# plp-ctop_2a.net
KiCad netlist of a schematic drawn in Altium Designer
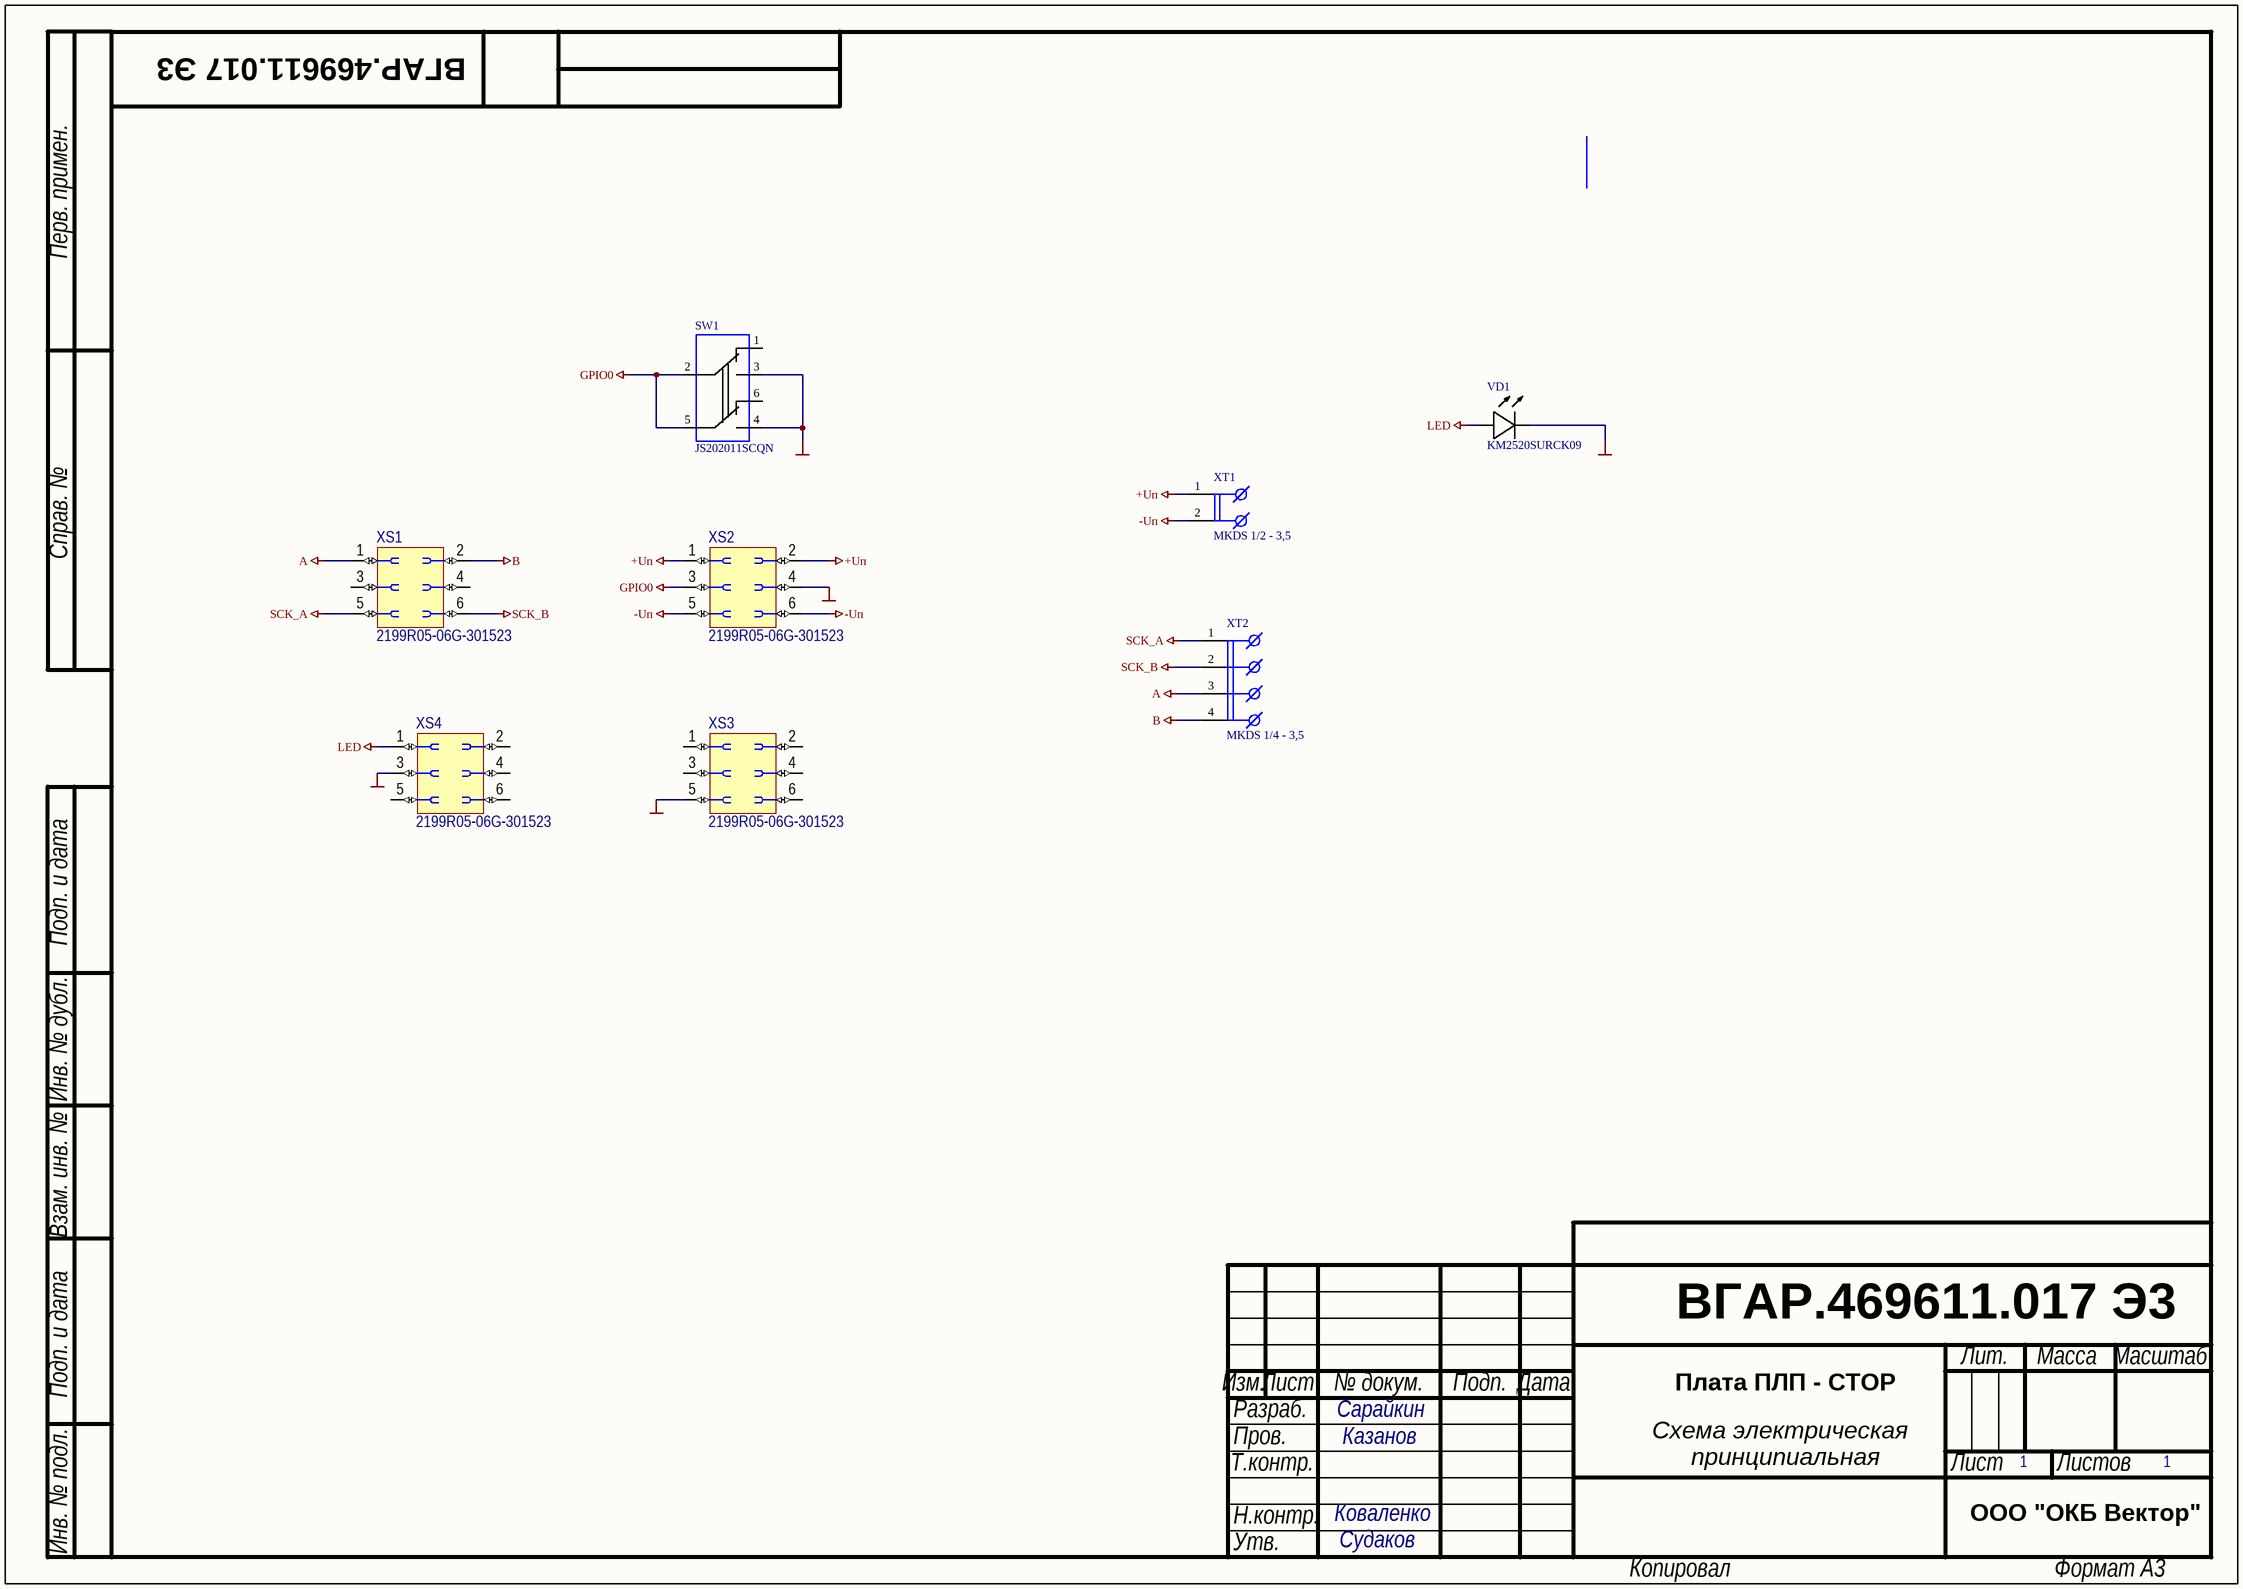
[diagram p0: plp-ctop_2a.SchDoc]

(export (version "E")
  (design (tool "Eeschema 10.0.6"))
  (components
    (comp (ref "SW1")
      (value "JS202011SCQN")
      (footprint "JS202011SCQN")
      (description "Переключатель")
      (fields
        (field (name "MANUFACTURER") "C&K Component")
        (field (name "REPLACEMENTPART1PARTNUMBER") "is-1390")
      )
      (libsource (lib "Switch") (part "JS202011SCQN"))
    )
    (comp (ref "VD1")
      (value "KM2520SURCK09")
      (footprint "KM2520SURCK09")
      (description "LED")
      (libsource (lib "Kingbright LED") (part "KM2520SURCK09"))
    )
    (comp (ref "XS1")
      (value "2199R05-06G-301523")
      (footprint "CON: PLL-6(2x3R1.27female)")
      (description "Step 1.27")
      (libsource (lib "connector") (part "2199R05-06G-301523In"))
    )
    (comp (ref "XS2")
      (value "2199R05-06G-301523")
      (footprint "CON: PLL-6(2x3R1.27female)")
      (description "Step 1.27")
      (libsource (lib "connector") (part "2199R05-06G-301523In"))
    )
    (comp (ref "XS3")
      (value "2199R05-06G-301523")
      (footprint "CON: PLL-6(2x3R1.27female)")
      (description "Step 1.27")
      (libsource (lib "connector") (part "2199R05-06G-301523In"))
    )
    (comp (ref "XS4")
      (value "2199R05-06G-301523")
      (footprint "CON: PLL-6(2x3R1.27female)")
      (description "Step 1.27")
      (libsource (lib "connector") (part "2199R05-06G-301523In"))
    )
    (comp (ref "XT1")
      (value "MKDS 1/2 - 3,5")
      (footprint "MKDS 1/2 - 3,5")
      (libsource (lib "Phoenixcontact Terminal Block") (part "MKDS 1/2 - 3,5"))
    )
    (comp (ref "XT2")
      (value "MKDS 1/4 - 3,5")
      (footprint "MKDS 1/4 - 3,5")
      (libsource (lib "Phoenixcontact Terminal Block") (part "MKDS 1/4 - 3,5"))
    )
  )
  (nets
    (net (code "1") (name "+Uп") (class "Default")
      (node (ref "XS2") (pin "1") (pinfunction "1_1") (pintype "bidirectional"))
      (node (ref "XS2") (pin "2") (pinfunction "2_2") (pintype "bidirectional"))
      (node (ref "XT1") (pin "1") (pintype "passive"))
    )
    (net (code "2") (name "-Uп") (class "Default")
      (node (ref "XS2") (pin "5") (pinfunction "5_5") (pintype "bidirectional"))
      (node (ref "XS2") (pin "6") (pinfunction "6_6") (pintype "bidirectional"))
      (node (ref "XT1") (pin "2") (pintype "passive"))
    )
    (net (code "3") (name "A") (class "Default")
      (node (ref "XS1") (pin "1") (pinfunction "1_1") (pintype "bidirectional"))
      (node (ref "XT2") (pin "3") (pintype "passive"))
    )
    (net (code "4") (name "B") (class "Default")
      (node (ref "XS1") (pin "2") (pinfunction "2_2") (pintype "bidirectional"))
      (node (ref "XT2") (pin "4") (pinfunction "4_4") (pintype "passive"))
    )
    (net (code "5") (name "GND") (class "Default")
      (node (ref "SW1") (pin "3") (pinfunction "3_3") (pintype "passive"))
      (node (ref "SW1") (pin "4") (pinfunction "4_4") (pintype "passive"))
      (node (ref "VD1") (pin "2") (pinfunction "K_2") (pintype "passive"))
      (node (ref "XS2") (pin "4") (pinfunction "4_4") (pintype "bidirectional"))
      (node (ref "XS3") (pin "5") (pinfunction "5_5") (pintype "bidirectional"))
      (node (ref "XS4") (pin "3") (pinfunction "3_3") (pintype "bidirectional"))
    )
    (net (code "6") (name "GPIO0") (class "Default")
      (node (ref "SW1") (pin "2") (pinfunction "2_2") (pintype "passive"))
      (node (ref "SW1") (pin "5") (pinfunction "5_5") (pintype "passive"))
      (node (ref "XS2") (pin "3") (pinfunction "3_3") (pintype "bidirectional"))
    )
    (net (code "7") (name "LED") (class "Default")
      (node (ref "VD1") (pin "1") (pinfunction "A_1") (pintype "passive"))
      (node (ref "XS4") (pin "1") (pinfunction "1_1") (pintype "bidirectional"))
    )
    (net (code "8") (name "SCK_A") (class "Default")
      (node (ref "XS1") (pin "5") (pinfunction "5_5") (pintype "bidirectional"))
      (node (ref "XT2") (pin "1") (pintype "passive"))
    )
    (net (code "9") (name "SCK_B") (class "Default")
      (node (ref "XS1") (pin "6") (pinfunction "6_6") (pintype "bidirectional"))
      (node (ref "XT2") (pin "2") (pintype "passive"))
    )
    (net (code "10") (name "unconnected-(SW1-Pad1)") (class "Default")
      (node (ref "SW1") (pin "1") (pinfunction "1_1") (pintype "passive"))
    )
    (net (code "11") (name "unconnected-(SW1-Pad6)") (class "Default")
      (node (ref "SW1") (pin "6") (pinfunction "6_6") (pintype "passive"))
    )
    (net (code "12") (name "unconnected-(XS1-Pad3)") (class "Default")
      (node (ref "XS1") (pin "3") (pinfunction "3_3") (pintype "bidirectional"))
    )
    (net (code "13") (name "unconnected-(XS1-Pad4)") (class "Default")
      (node (ref "XS1") (pin "4") (pinfunction "4_4") (pintype "bidirectional"))
    )
    (net (code "14") (name "unconnected-(XS3-Pad1)") (class "Default")
      (node (ref "XS3") (pin "1") (pinfunction "1_1") (pintype "bidirectional"))
    )
    (net (code "15") (name "unconnected-(XS3-Pad2)") (class "Default")
      (node (ref "XS3") (pin "2") (pinfunction "2_2") (pintype "bidirectional"))
    )
    (net (code "16") (name "unconnected-(XS3-Pad3)") (class "Default")
      (node (ref "XS3") (pin "3") (pinfunction "3_3") (pintype "bidirectional"))
    )
    (net (code "17") (name "unconnected-(XS3-Pad4)") (class "Default")
      (node (ref "XS3") (pin "4") (pinfunction "4_4") (pintype "bidirectional"))
    )
    (net (code "18") (name "unconnected-(XS3-Pad6)") (class "Default")
      (node (ref "XS3") (pin "6") (pinfunction "6_6") (pintype "bidirectional"))
    )
    (net (code "19") (name "unconnected-(XS4-Pad2)") (class "Default")
      (node (ref "XS4") (pin "2") (pinfunction "2_2") (pintype "bidirectional"))
    )
    (net (code "20") (name "unconnected-(XS4-Pad4)") (class "Default")
      (node (ref "XS4") (pin "4") (pinfunction "4_4") (pintype "bidirectional"))
    )
    (net (code "21") (name "unconnected-(XS4-Pad5)") (class "Default")
      (node (ref "XS4") (pin "5") (pinfunction "5_5") (pintype "bidirectional"))
    )
    (net (code "22") (name "unconnected-(XS4-Pad6)") (class "Default")
      (node (ref "XS4") (pin "6") (pinfunction "6_6") (pintype "bidirectional"))
    )
  )
)
